# GPIO.net
KiCad netlist of a schematic drawn in Altium Designer
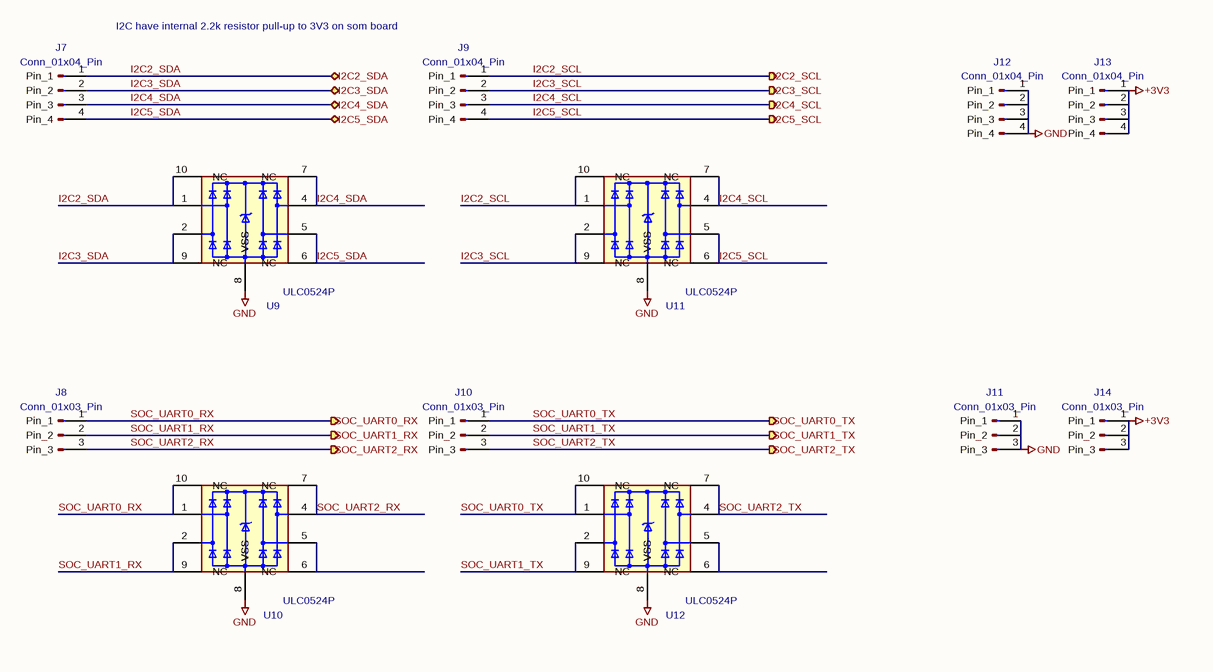
[diagram p0: GPIO.SchDoc]

(export (version "E")
  (design (tool "Eeschema 10.0.6"))
  (components
    (comp (ref "J7") (value "Conn_01x04_Pin") (libsource (lib "Connector") (part "Conn_01x04_Pin")))
    (comp (ref "J8") (value "Conn_01x03_Pin") (libsource (lib "Connector") (part "Conn_01x03_Pin")))
    (comp (ref "J9") (value "Conn_01x04_Pin") (libsource (lib "Connector") (part "Conn_01x04_Pin")))
    (comp (ref "J10") (value "Conn_01x03_Pin") (libsource (lib "Connector") (part "Conn_01x03_Pin")))
    (comp (ref "J11") (value "Conn_01x03_Pin") (libsource (lib "Connector") (part "Conn_01x03_Pin")))
    (comp (ref "J12") (value "Conn_01x04_Pin") (libsource (lib "Connector") (part "Conn_01x04_Pin")))
    (comp (ref "J13") (value "Conn_01x04_Pin") (libsource (lib "Connector") (part "Conn_01x04_Pin")))
    (comp (ref "J14") (value "Conn_01x03_Pin") (libsource (lib "Connector") (part "Conn_01x03_Pin")))
    (comp (ref "U9") (value "ULC0524P") (libsource (lib "Power_Protection") (part "D3V3XA4B10LP")))
    (comp (ref "U10") (value "ULC0524P") (libsource (lib "Power_Protection") (part "D3V3XA4B10LP")))
    (comp (ref "U11") (value "ULC0524P") (libsource (lib "Power_Protection") (part "D3V3XA4B10LP")))
    (comp (ref "U12") (value "ULC0524P") (libsource (lib "Power_Protection") (part "D3V3XA4B10LP")))
  )
  (nets
    (net (code "1") (name "+3V3") (class "Default")
      (node (ref "J13") (pin "1") (pinfunction "Pin_1_1") (pintype "passive"))
      (node (ref "J13") (pin "2") (pinfunction "Pin_2_2") (pintype "passive"))
      (node (ref "J13") (pin "3") (pinfunction "Pin_3_3") (pintype "passive"))
      (node (ref "J13") (pin "4") (pinfunction "Pin_4_4") (pintype "passive"))
      (node (ref "J14") (pin "1") (pinfunction "Pin_1_1") (pintype "passive"))
      (node (ref "J14") (pin "2") (pinfunction "Pin_2_2") (pintype "passive"))
      (node (ref "J14") (pin "3") (pinfunction "Pin_3_3") (pintype "passive"))
    )
    (net (code "2") (name "/I2C2_SCL") (class "Default")
      (node (ref "J9") (pin "1") (pinfunction "Pin_1_1") (pintype "passive"))
      (node (ref "U11") (pin "1") (pinfunction "1_1") (pintype "passive"))
      (node (ref "U11") (pin "10") (pinfunction "NC_10") (pintype "passive"))
    )
    (net (code "3") (name "/I2C2_SDA") (class "Default")
      (node (ref "J7") (pin "1") (pinfunction "Pin_1_1") (pintype "passive"))
      (node (ref "U9") (pin "1") (pinfunction "1_1") (pintype "passive"))
      (node (ref "U9") (pin "10") (pinfunction "NC_10") (pintype "passive"))
    )
    (net (code "4") (name "/I2C3_SCL") (class "Default")
      (node (ref "J9") (pin "2") (pinfunction "Pin_2_2") (pintype "passive"))
      (node (ref "U11") (pin "2") (pinfunction "2_2") (pintype "passive"))
      (node (ref "U11") (pin "9") (pinfunction "NC_9") (pintype "passive"))
    )
    (net (code "5") (name "/I2C3_SDA") (class "Default")
      (node (ref "J7") (pin "2") (pinfunction "Pin_2_2") (pintype "passive"))
      (node (ref "U9") (pin "2") (pinfunction "2_2") (pintype "passive"))
      (node (ref "U9") (pin "9") (pinfunction "NC_9") (pintype "passive"))
    )
    (net (code "6") (name "/I2C4_SCL") (class "Default")
      (node (ref "J9") (pin "3") (pinfunction "Pin_3_3") (pintype "passive"))
      (node (ref "U11") (pin "4") (pinfunction "4_4") (pintype "passive"))
      (node (ref "U11") (pin "7") (pinfunction "NC_7") (pintype "passive"))
    )
    (net (code "7") (name "/I2C4_SDA") (class "Default")
      (node (ref "J7") (pin "3") (pinfunction "Pin_3_3") (pintype "passive"))
      (node (ref "U9") (pin "4") (pinfunction "4_4") (pintype "passive"))
      (node (ref "U9") (pin "7") (pinfunction "NC_7") (pintype "passive"))
    )
    (net (code "8") (name "/I2C5_SCL") (class "Default")
      (node (ref "J9") (pin "4") (pinfunction "Pin_4_4") (pintype "passive"))
      (node (ref "U11") (pin "5") (pinfunction "5_5") (pintype "passive"))
      (node (ref "U11") (pin "6") (pinfunction "NC_6") (pintype "passive"))
    )
    (net (code "9") (name "/I2C5_SDA") (class "Default")
      (node (ref "J7") (pin "4") (pinfunction "Pin_4_4") (pintype "passive"))
      (node (ref "U9") (pin "5") (pinfunction "5_5") (pintype "passive"))
      (node (ref "U9") (pin "6") (pinfunction "NC_6") (pintype "passive"))
    )
    (net (code "10") (name "/SOC_UART0_RX") (class "Default")
      (node (ref "J8") (pin "1") (pinfunction "Pin_1_1") (pintype "passive"))
      (node (ref "U10") (pin "1") (pinfunction "1_1") (pintype "passive"))
      (node (ref "U10") (pin "10") (pinfunction "NC_10") (pintype "passive"))
    )
    (net (code "11") (name "/SOC_UART0_TX") (class "Default")
      (node (ref "J10") (pin "1") (pinfunction "Pin_1_1") (pintype "passive"))
      (node (ref "U12") (pin "1") (pinfunction "1_1") (pintype "passive"))
      (node (ref "U12") (pin "10") (pinfunction "NC_10") (pintype "passive"))
    )
    (net (code "12") (name "/SOC_UART1_RX") (class "Default")
      (node (ref "J8") (pin "2") (pinfunction "Pin_2_2") (pintype "passive"))
      (node (ref "U10") (pin "2") (pinfunction "2_2") (pintype "passive"))
      (node (ref "U10") (pin "9") (pinfunction "NC_9") (pintype "passive"))
    )
    (net (code "13") (name "/SOC_UART1_TX") (class "Default")
      (node (ref "J10") (pin "2") (pinfunction "Pin_2_2") (pintype "passive"))
      (node (ref "U12") (pin "2") (pinfunction "2_2") (pintype "passive"))
      (node (ref "U12") (pin "9") (pinfunction "NC_9") (pintype "passive"))
    )
    (net (code "14") (name "/SOC_UART2_RX") (class "Default")
      (node (ref "J8") (pin "3") (pinfunction "Pin_3_3") (pintype "passive"))
      (node (ref "U10") (pin "4") (pinfunction "4_4") (pintype "passive"))
      (node (ref "U10") (pin "7") (pinfunction "NC_7") (pintype "passive"))
    )
    (net (code "15") (name "/SOC_UART2_TX") (class "Default")
      (node (ref "J10") (pin "3") (pinfunction "Pin_3_3") (pintype "passive"))
      (node (ref "U12") (pin "4") (pinfunction "4_4") (pintype "passive"))
      (node (ref "U12") (pin "7") (pinfunction "NC_7") (pintype "passive"))
    )
    (net (code "16") (name "GND") (class "Default")
      (node (ref "J11") (pin "1") (pinfunction "Pin_1_1") (pintype "passive"))
      (node (ref "J11") (pin "2") (pinfunction "Pin_2_2") (pintype "passive"))
      (node (ref "J11") (pin "3") (pinfunction "Pin_3_3") (pintype "passive"))
      (node (ref "J12") (pin "1") (pinfunction "Pin_1_1") (pintype "passive"))
      (node (ref "J12") (pin "2") (pinfunction "Pin_2_2") (pintype "passive"))
      (node (ref "J12") (pin "3") (pinfunction "Pin_3_3") (pintype "passive"))
      (node (ref "J12") (pin "4") (pinfunction "Pin_4_4") (pintype "passive"))
      (node (ref "U10") (pin "3") (pinfunction "VSS_3") (pintype "passive"))
      (node (ref "U10") (pin "8") (pinfunction "VSS_8") (pintype "passive"))
      (node (ref "U11") (pin "3") (pinfunction "VSS_3") (pintype "passive"))
      (node (ref "U11") (pin "8") (pinfunction "VSS_8") (pintype "passive"))
      (node (ref "U12") (pin "3") (pinfunction "VSS_3") (pintype "passive"))
      (node (ref "U12") (pin "8") (pinfunction "VSS_8") (pintype "passive"))
      (node (ref "U9") (pin "3") (pinfunction "VSS_3") (pintype "passive"))
      (node (ref "U9") (pin "8") (pinfunction "VSS_8") (pintype "passive"))
    )
    (net (code "17") (name "Net-(U10-NC-Pad6)") (class "Default")
      (node (ref "U10") (pin "5") (pinfunction "5_5") (pintype "passive"))
      (node (ref "U10") (pin "6") (pinfunction "NC_6") (pintype "passive"))
    )
    (net (code "18") (name "Net-(U12-NC-Pad6)") (class "Default")
      (node (ref "U12") (pin "5") (pinfunction "5_5") (pintype "passive"))
      (node (ref "U12") (pin "6") (pinfunction "NC_6") (pintype "passive"))
    )
  )
)
